# tinyLIPO.net
KiCad netlist of a schematic drawn in EAGLE
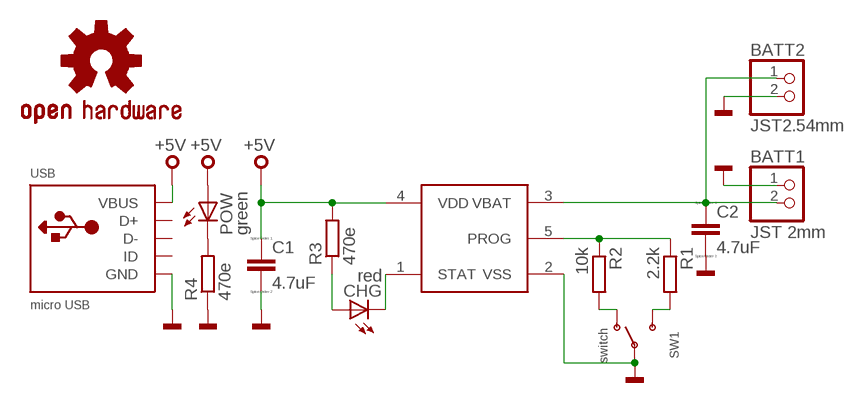
[diagram p0: schematic, sheet 1]

(export (version "E")
  (design (tool "Eeschema 10.0.6"))
  (components
    (comp (ref "BATT1")
      (value "JST 2mm")
      (footprint "eagle-import:JSTPH2")
      (libsource (lib "eagle-import") (part "JST_2PIN"))
    )
    (comp (ref "BATT2")
      (value "JST2.54mm")
      (footprint "eagle-import:1X02_OVAL")
      (libsource (lib "eagle-import") (part "HEADER-1X2"))
    )
    (comp (ref "C1")
      (value "4.7uF")
      (footprint "eagle-import:C0805")
      (libsource (lib "eagle-import") (part "C-EUC0805"))
    )
    (comp (ref "C2")
      (value "4.7uF")
      (footprint "eagle-import:C0805")
      (libsource (lib "eagle-import") (part "C-EUC0805"))
    )
    (comp (ref "CHG")
      (value "red")
      (footprint "eagle-import:CHIPLED_0805")
      (libsource (lib "eagle-import") (part "LEDCHIPLED_0805"))
    )
    (comp (ref "IC1")
      (value "MCP73831")
      (footprint "eagle-import:SOT23-5")
      (libsource (lib "eagle-import") (part "MCP73831"))
    )
    (comp (ref "LOGO1")
      (value "OSHW-LOGOM")
      (footprint "eagle-import:OSHW-LOGO-M")
      (libsource (lib "eagle-import") (part "OSHW-LOGOM"))
    )
    (comp (ref "POW")
      (value "green")
      (footprint "eagle-import:CHIPLED_0805")
      (libsource (lib "eagle-import") (part "LEDCHIPLED_0805"))
    )
    (comp (ref "R1")
      (value "2.2k")
      (footprint "eagle-import:M0805")
      (libsource (lib "eagle-import") (part "R-EU_M0805"))
    )
    (comp (ref "R2")
      (value "10k")
      (footprint "eagle-import:M0805")
      (libsource (lib "eagle-import") (part "R-EU_M0805"))
    )
    (comp (ref "R3")
      (value "470e")
      (footprint "eagle-import:M0805")
      (libsource (lib "eagle-import") (part "R-EU_M0805"))
    )
    (comp (ref "R4")
      (value "470e")
      (footprint "eagle-import:M0805")
      (libsource (lib "eagle-import") (part "R-EU_M0805"))
    )
    (comp (ref "SW1")
      (value "switch")
      (footprint "eagle-import:SPDT_SMT_SSSS811101")
      (libsource (lib "eagle-import") (part "SWITCH_SPDT"))
    )
    (comp (ref "USB")
      (value "micro USB")
      (footprint "eagle-import:USB-MINIB_LARGER")
      (libsource (lib "eagle-import") (part "USBMINIBLARGE"))
    )
  )
  (nets
    (net (code "1") (name "+5V") (class "Default")
      (node (ref "C1") (pin "1") (pinfunction "1_1") (pintype "passive"))
      (node (ref "IC1") (pin "4") (pinfunction "VDD_4") (pintype "bidirectional"))
      (node (ref "POW") (pin "A") (pinfunction "A_A") (pintype "passive"))
      (node (ref "R3") (pin "2") (pinfunction "2_2") (pintype "passive"))
      (node (ref "USB") (pin "VBUS") (pinfunction "VBUS_VBUS") (pintype "power_in"))
    )
    (net (code "2") (name "GND") (class "Default")
      (node (ref "BATT1") (pin "1") (pinfunction "1_1") (pintype "passive"))
      (node (ref "BATT2") (pin "2") (pinfunction "2_2") (pintype "passive"))
      (node (ref "C1") (pin "2") (pinfunction "2_2") (pintype "passive"))
      (node (ref "C2") (pin "2") (pinfunction "2_2") (pintype "passive"))
      (node (ref "IC1") (pin "2") (pinfunction "VSS_2") (pintype "bidirectional"))
      (node (ref "R4") (pin "1") (pinfunction "1_1") (pintype "passive"))
      (node (ref "SW1") (pin "B") (pinfunction "P_B") (pintype "passive"))
      (node (ref "USB") (pin "GND") (pinfunction "GND_GND") (pintype "power_in"))
    )
    (net (code "3") (name "Net-(CHG-PadA)") (class "Default")
      (node (ref "CHG") (pin "A") (pinfunction "A_A") (pintype "passive"))
      (node (ref "R3") (pin "1") (pinfunction "1_1") (pintype "passive"))
    )
    (net (code "4") (name "Net-(IC1-PROG)") (class "Default")
      (node (ref "IC1") (pin "5") (pinfunction "PROG_5") (pintype "bidirectional"))
      (node (ref "R1") (pin "1") (pinfunction "1_1") (pintype "passive"))
      (node (ref "R2") (pin "1") (pinfunction "1_1") (pintype "passive"))
    )
    (net (code "5") (name "Net-(IC1-STAT)") (class "Default")
      (node (ref "CHG") (pin "C") (pinfunction "C_C") (pintype "passive"))
      (node (ref "IC1") (pin "1") (pinfunction "STAT_1") (pintype "bidirectional"))
    )
    (net (code "6") (name "Net-(IC1-VBAT)") (class "Default")
      (node (ref "BATT1") (pin "2") (pinfunction "2_2") (pintype "passive"))
      (node (ref "BATT2") (pin "1") (pinfunction "1_1") (pintype "passive"))
      (node (ref "C2") (pin "1") (pinfunction "1_1") (pintype "passive"))
      (node (ref "IC1") (pin "3") (pinfunction "VBAT_3") (pintype "bidirectional"))
    )
    (net (code "7") (name "Net-(POW-PadC)") (class "Default")
      (node (ref "POW") (pin "C") (pinfunction "C_C") (pintype "passive"))
      (node (ref "R4") (pin "2") (pinfunction "2_2") (pintype "passive"))
    )
    (net (code "8") (name "Net-(SW1-O)") (class "Default")
      (node (ref "R2") (pin "2") (pinfunction "2_2") (pintype "passive"))
      (node (ref "SW1") (pin "A") (pinfunction "O_A") (pintype "passive"))
    )
    (net (code "9") (name "Net-(SW1-S)") (class "Default")
      (node (ref "R1") (pin "2") (pinfunction "2_2") (pintype "passive"))
      (node (ref "SW1") (pin "C") (pinfunction "S_C") (pintype "passive"))
    )
    (net (code "10") (name "unconnected-(USB-PadD+)") (class "Default")
      (node (ref "USB") (pin "D+") (pinfunction "D+_D+") (pintype "bidirectional"))
    )
    (net (code "11") (name "unconnected-(USB-PadD-)") (class "Default")
      (node (ref "USB") (pin "D-") (pinfunction "D-_D-") (pintype "bidirectional"))
    )
    (net (code "12") (name "unconnected-(USB-PadID)") (class "Default")
      (node (ref "USB") (pin "ID") (pinfunction "ID_ID") (pintype "bidirectional"))
    )
  )
)
